# Kivipallur_joonis1.net
KiCad netlist of a schematic drawn in Altium Designer
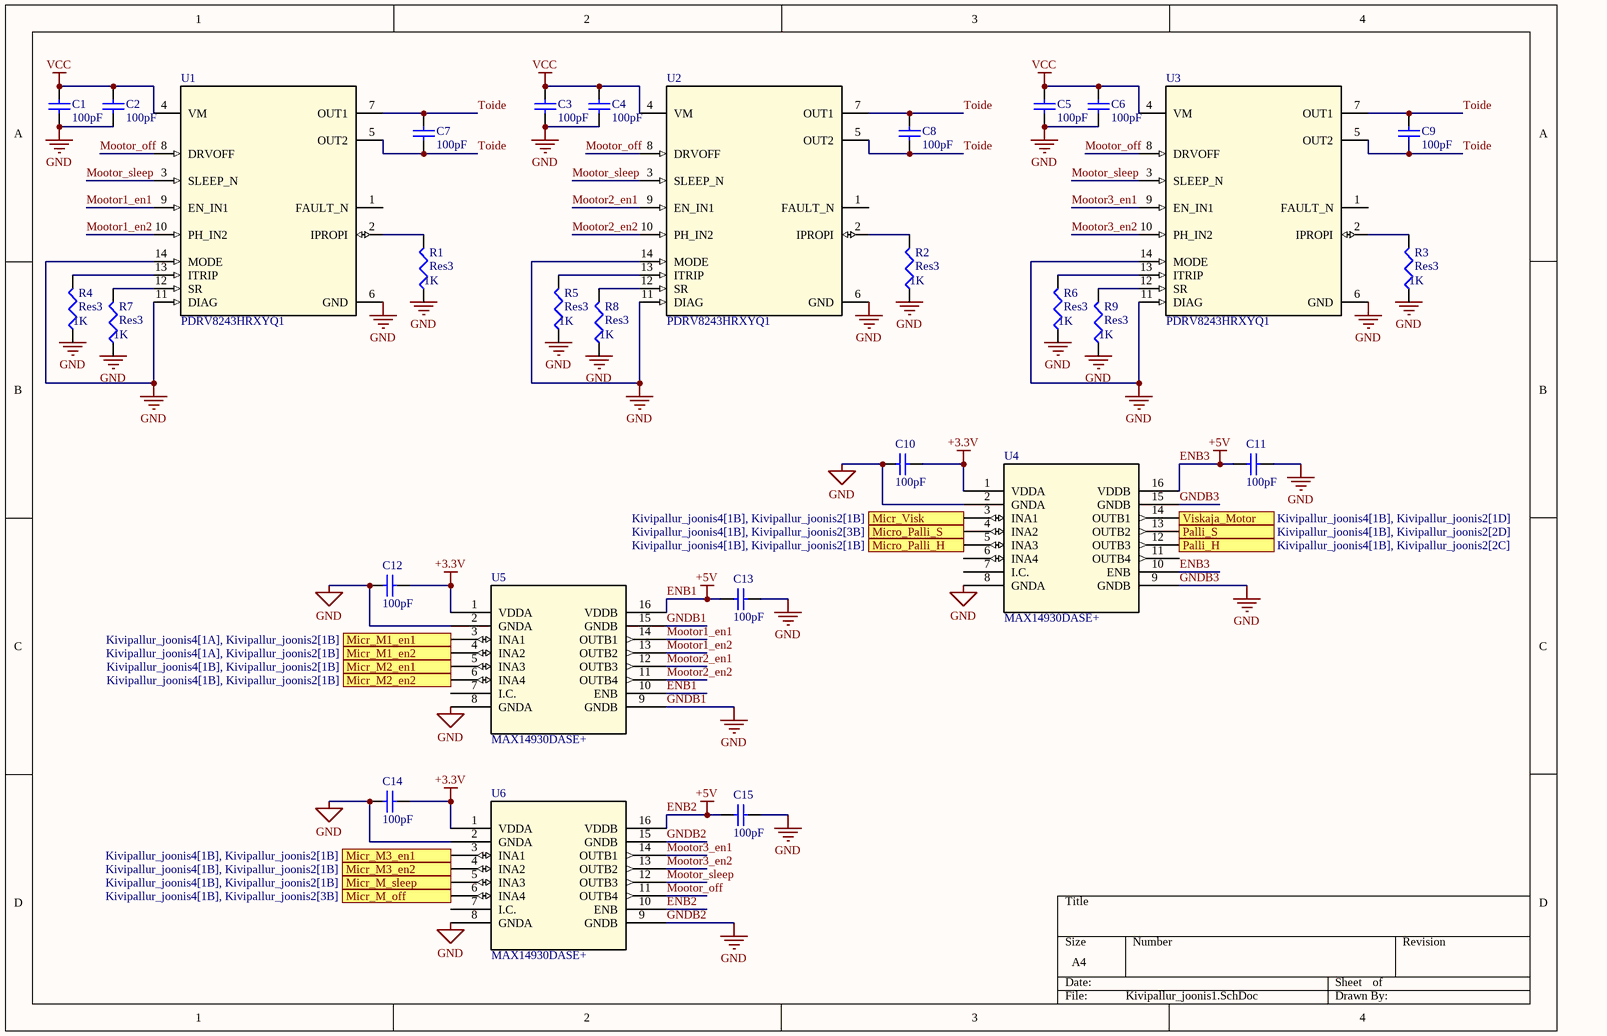
[diagram p0: Kivipallur_joonis1.SchDoc]

(export (version "E")
  (design (tool "Eeschema 10.0.6"))
  (components
    (comp (ref "C1")
      (value "100pF")
      (footprint "C1206")
      (description "Capacitor (Semiconductor SIM Model)")
      (fields (field (name "Comment") "Cap Semi") (field (name "PUBLISHER") "Altium Limited"))
      (libsource (lib "Miscellaneous Devices") (part "Cap Semi"))
    )
    (comp (ref "C2")
      (value "100pF")
      (footprint "C1206")
      (description "Capacitor (Semiconductor SIM Model)")
      (fields (field (name "Comment") "Cap Semi") (field (name "PUBLISHER") "Altium Limited"))
      (libsource (lib "Miscellaneous Devices") (part "Cap Semi"))
    )
    (comp (ref "C3")
      (value "100pF")
      (footprint "C1206")
      (description "Capacitor (Semiconductor SIM Model)")
      (fields (field (name "Comment") "Cap Semi") (field (name "PUBLISHER") "Altium Limited"))
      (libsource (lib "Miscellaneous Devices") (part "Cap Semi"))
    )
    (comp (ref "C4")
      (value "100pF")
      (footprint "C1206")
      (description "Capacitor (Semiconductor SIM Model)")
      (fields (field (name "Comment") "Cap Semi") (field (name "PUBLISHER") "Altium Limited"))
      (libsource (lib "Miscellaneous Devices") (part "Cap Semi"))
    )
    (comp (ref "C5")
      (value "100pF")
      (footprint "C1206")
      (description "Capacitor (Semiconductor SIM Model)")
      (fields (field (name "Comment") "Cap Semi") (field (name "PUBLISHER") "Altium Limited"))
      (libsource (lib "Miscellaneous Devices") (part "Cap Semi"))
    )
    (comp (ref "C6")
      (value "100pF")
      (footprint "C1206")
      (description "Capacitor (Semiconductor SIM Model)")
      (fields (field (name "Comment") "Cap Semi") (field (name "PUBLISHER") "Altium Limited"))
      (libsource (lib "Miscellaneous Devices") (part "Cap Semi"))
    )
    (comp (ref "C7")
      (value "100pF")
      (footprint "C1206")
      (description "Capacitor (Semiconductor SIM Model)")
      (fields (field (name "Comment") "Cap Semi") (field (name "PUBLISHER") "Altium Limited"))
      (libsource (lib "Miscellaneous Devices") (part "Cap Semi"))
    )
    (comp (ref "C8")
      (value "100pF")
      (footprint "C1206")
      (description "Capacitor (Semiconductor SIM Model)")
      (fields (field (name "Comment") "Cap Semi") (field (name "PUBLISHER") "Altium Limited"))
      (libsource (lib "Miscellaneous Devices") (part "Cap Semi"))
    )
    (comp (ref "C9")
      (value "100pF")
      (footprint "C1206")
      (description "Capacitor (Semiconductor SIM Model)")
      (fields (field (name "Comment") "Cap Semi") (field (name "PUBLISHER") "Altium Limited"))
      (libsource (lib "Miscellaneous Devices") (part "Cap Semi"))
    )
    (comp (ref "C10")
      (value "100pF")
      (footprint "C1206")
      (description "Capacitor (Semiconductor SIM Model)")
      (fields (field (name "Comment") "Cap Semi") (field (name "PUBLISHER") "Altium Limited"))
      (libsource (lib "Miscellaneous Devices") (part "Cap Semi"))
    )
    (comp (ref "C11")
      (value "100pF")
      (footprint "C1206")
      (description "Capacitor (Semiconductor SIM Model)")
      (fields (field (name "Comment") "Cap Semi") (field (name "PUBLISHER") "Altium Limited"))
      (libsource (lib "Miscellaneous Devices") (part "Cap Semi"))
    )
    (comp (ref "C12")
      (value "100pF")
      (footprint "C1206")
      (description "Capacitor (Semiconductor SIM Model)")
      (fields (field (name "Comment") "Cap Semi") (field (name "PUBLISHER") "Altium Limited"))
      (libsource (lib "Miscellaneous Devices") (part "Cap Semi"))
    )
    (comp (ref "C13")
      (value "100pF")
      (footprint "C1206")
      (description "Capacitor (Semiconductor SIM Model)")
      (fields (field (name "Comment") "Cap Semi") (field (name "PUBLISHER") "Altium Limited"))
      (libsource (lib "Miscellaneous Devices") (part "Cap Semi"))
    )
    (comp (ref "C14")
      (value "100pF")
      (footprint "C1206")
      (description "Capacitor (Semiconductor SIM Model)")
      (fields (field (name "Comment") "Cap Semi") (field (name "PUBLISHER") "Altium Limited"))
      (libsource (lib "Miscellaneous Devices") (part "Cap Semi"))
    )
    (comp (ref "C15")
      (value "100pF")
      (footprint "C1206")
      (description "Capacitor (Semiconductor SIM Model)")
      (fields (field (name "Comment") "Cap Semi") (field (name "PUBLISHER") "Altium Limited"))
      (libsource (lib "Miscellaneous Devices") (part "Cap Semi"))
    )
    (comp (ref "R1")
      (value "Res3")
      (footprint "J1-0603")
      (description "Resistor")
      (fields (field (name "ALTIUM_VALUE") "1K") (field (name "PUBLISHER") "Altium Limited"))
      (libsource (lib "Miscellaneous Devices") (part "Res3"))
    )
    (comp (ref "R2")
      (value "Res3")
      (footprint "J1-0603")
      (description "Resistor")
      (fields (field (name "ALTIUM_VALUE") "1K") (field (name "PUBLISHER") "Altium Limited"))
      (libsource (lib "Miscellaneous Devices") (part "Res3"))
    )
    (comp (ref "R3")
      (value "Res3")
      (footprint "J1-0603")
      (description "Resistor")
      (fields (field (name "ALTIUM_VALUE") "1K") (field (name "PUBLISHER") "Altium Limited"))
      (libsource (lib "Miscellaneous Devices") (part "Res3"))
    )
    (comp (ref "R4")
      (value "Res3")
      (footprint "J1-0603")
      (description "Resistor")
      (fields (field (name "ALTIUM_VALUE") "1K") (field (name "PUBLISHER") "Altium Limited"))
      (libsource (lib "Miscellaneous Devices") (part "Res3"))
    )
    (comp (ref "R5")
      (value "Res3")
      (footprint "J1-0603")
      (description "Resistor")
      (fields (field (name "ALTIUM_VALUE") "1K") (field (name "PUBLISHER") "Altium Limited"))
      (libsource (lib "Miscellaneous Devices") (part "Res3"))
    )
    (comp (ref "R6")
      (value "Res3")
      (footprint "J1-0603")
      (description "Resistor")
      (fields (field (name "ALTIUM_VALUE") "1K") (field (name "PUBLISHER") "Altium Limited"))
      (libsource (lib "Miscellaneous Devices") (part "Res3"))
    )
    (comp (ref "R7")
      (value "Res3")
      (footprint "J1-0603")
      (description "Resistor")
      (fields (field (name "ALTIUM_VALUE") "1K") (field (name "PUBLISHER") "Altium Limited"))
      (libsource (lib "Miscellaneous Devices") (part "Res3"))
    )
    (comp (ref "R8")
      (value "Res3")
      (footprint "J1-0603")
      (description "Resistor")
      (fields (field (name "ALTIUM_VALUE") "1K") (field (name "PUBLISHER") "Altium Limited"))
      (libsource (lib "Miscellaneous Devices") (part "Res3"))
    )
    (comp (ref "R9")
      (value "Res3")
      (footprint "J1-0603")
      (description "Resistor")
      (fields (field (name "ALTIUM_VALUE") "1K") (field (name "PUBLISHER") "Altium Limited"))
      (libsource (lib "Miscellaneous Devices") (part "Res3"))
    )
    (comp (ref "U1")
      (value "PDRV8243HRXYQ1")
      (footprint "RXY0014A-MFG")
      (description "No Description Available")
      (fields (field (name "COPYRIGHT") "Copyright (C) 2022 Ultra Librarian. All rights reserved."))
      (libsource (lib "PDRV8243HRXYQ1") (part "PDRV8243HRXYQ1"))
    )
    (comp (ref "U2")
      (value "PDRV8243HRXYQ1")
      (footprint "RXY0014A-MFG")
      (description "No Description Available")
      (fields (field (name "COPYRIGHT") "Copyright (C) 2022 Ultra Librarian. All rights reserved."))
      (libsource (lib "PDRV8243HRXYQ1") (part "PDRV8243HRXYQ1"))
    )
    (comp (ref "U3")
      (value "PDRV8243HRXYQ1")
      (footprint "RXY0014A-MFG")
      (description "No Description Available")
      (fields (field (name "COPYRIGHT") "Copyright (C) 2022 Ultra Librarian. All rights reserved."))
      (libsource (lib "PDRV8243HRXYQ1") (part "PDRV8243HRXYQ1"))
    )
    (comp (ref "U4")
      (value "MAX14930DASE+")
      (footprint "21-0041_S16+1_MXM")
      (description "No Description Available")
      (fields (field (name "COPYRIGHT") "Copyright (C) 2022 Ultra Librarian. All rights reserved."))
      (libsource (lib "MAX14930DASE&plus_") (part "MAX14930DASE+"))
    )
    (comp (ref "U5")
      (value "MAX14930DASE+")
      (footprint "21-0041_S16+1_MXM")
      (description "No Description Available")
      (fields (field (name "COPYRIGHT") "Copyright (C) 2022 Ultra Librarian. All rights reserved."))
      (libsource (lib "MAX14930DASE&plus_") (part "MAX14930DASE+"))
    )
    (comp (ref "U6")
      (value "MAX14930DASE+")
      (footprint "21-0041_S16+1_MXM")
      (description "No Description Available")
      (fields (field (name "COPYRIGHT") "Copyright (C) 2022 Ultra Librarian. All rights reserved."))
      (libsource (lib "MAX14930DASE&plus_") (part "MAX14930DASE+"))
    )
  )
  (nets
    (net (code "1") (name "+3.3V") (class "Default")
      (node (ref "C10") (pin "2") (pinfunction "2_2") (pintype "passive"))
      (node (ref "C12") (pin "2") (pinfunction "2_2") (pintype "passive"))
      (node (ref "C14") (pin "2") (pinfunction "2_2") (pintype "passive"))
      (node (ref "U4") (pin "1") (pinfunction "VDDA_1") (pintype "power_in"))
      (node (ref "U5") (pin "1") (pinfunction "VDDA_1") (pintype "power_in"))
      (node (ref "U6") (pin "1") (pinfunction "VDDA_1") (pintype "power_in"))
    )
    (net (code "2") (name "+5V") (class "Default")
      (node (ref "C11") (pin "1") (pinfunction "1_1") (pintype "passive"))
      (node (ref "C13") (pin "1") (pinfunction "1_1") (pintype "passive"))
      (node (ref "C15") (pin "1") (pinfunction "1_1") (pintype "passive"))
      (node (ref "U4") (pin "10") (pinfunction "ENB_10") (pintype "passive"))
      (node (ref "U4") (pin "16") (pinfunction "VDDB_16") (pintype "power_in"))
      (node (ref "U5") (pin "10") (pinfunction "ENB_10") (pintype "passive"))
      (node (ref "U5") (pin "16") (pinfunction "VDDB_16") (pintype "power_in"))
      (node (ref "U6") (pin "10") (pinfunction "ENB_10") (pintype "passive"))
      (node (ref "U6") (pin "16") (pinfunction "VDDB_16") (pintype "power_in"))
    )
    (net (code "3") (name "/Micr_M1_en1") (class "Default")
      (node (ref "U5") (pin "3") (pinfunction "INA1_3") (pintype "bidirectional"))
    )
    (net (code "4") (name "/Micr_M1_en2") (class "Default")
      (node (ref "U5") (pin "4") (pinfunction "INA2_4") (pintype "bidirectional"))
    )
    (net (code "5") (name "/Micr_M2_en1") (class "Default")
      (node (ref "U5") (pin "5") (pinfunction "INA3_5") (pintype "bidirectional"))
    )
    (net (code "6") (name "/Micr_M2_en2") (class "Default")
      (node (ref "U5") (pin "6") (pinfunction "INA4_6") (pintype "bidirectional"))
    )
    (net (code "7") (name "/Micr_M3_en1") (class "Default")
      (node (ref "U6") (pin "3") (pinfunction "INA1_3") (pintype "bidirectional"))
    )
    (net (code "8") (name "/Micr_M3_en2") (class "Default")
      (node (ref "U6") (pin "4") (pinfunction "INA2_4") (pintype "bidirectional"))
    )
    (net (code "9") (name "/Micr_M_off") (class "Default")
      (node (ref "U6") (pin "6") (pinfunction "INA4_6") (pintype "bidirectional"))
    )
    (net (code "10") (name "/Micr_M_sleep") (class "Default")
      (node (ref "U6") (pin "5") (pinfunction "INA3_5") (pintype "bidirectional"))
    )
    (net (code "11") (name "/Micr_Visk") (class "Default")
      (node (ref "U4") (pin "3") (pinfunction "INA1_3") (pintype "bidirectional"))
    )
    (net (code "12") (name "/Micro_Palli_H") (class "Default")
      (node (ref "U4") (pin "5") (pinfunction "INA3_5") (pintype "bidirectional"))
    )
    (net (code "13") (name "/Micro_Palli_S") (class "Default")
      (node (ref "U4") (pin "4") (pinfunction "INA2_4") (pintype "bidirectional"))
    )
    (net (code "14") (name "/Mootor1_en1") (class "Default")
      (node (ref "U1") (pin "9") (pinfunction "EN_IN1_9") (pintype "input"))
      (node (ref "U5") (pin "14") (pinfunction "OUTB1_14") (pintype "output"))
    )
    (net (code "15") (name "/Mootor1_en2") (class "Default")
      (node (ref "U1") (pin "10") (pinfunction "PH_IN2_10") (pintype "input"))
      (node (ref "U5") (pin "13") (pinfunction "OUTB2_13") (pintype "output"))
    )
    (net (code "16") (name "/Mootor2_en1") (class "Default")
      (node (ref "U2") (pin "9") (pinfunction "EN_IN1_9") (pintype "input"))
      (node (ref "U5") (pin "12") (pinfunction "OUTB3_12") (pintype "output"))
    )
    (net (code "17") (name "/Mootor2_en2") (class "Default")
      (node (ref "U2") (pin "10") (pinfunction "PH_IN2_10") (pintype "input"))
      (node (ref "U5") (pin "11") (pinfunction "OUTB4_11") (pintype "output"))
    )
    (net (code "18") (name "/Mootor3_en1") (class "Default")
      (node (ref "U3") (pin "9") (pinfunction "EN_IN1_9") (pintype "input"))
      (node (ref "U6") (pin "14") (pinfunction "OUTB1_14") (pintype "output"))
    )
    (net (code "19") (name "/Mootor3_en2") (class "Default")
      (node (ref "U3") (pin "10") (pinfunction "PH_IN2_10") (pintype "input"))
      (node (ref "U6") (pin "13") (pinfunction "OUTB2_13") (pintype "output"))
    )
    (net (code "20") (name "/Mootor_off") (class "Default")
      (node (ref "U1") (pin "8") (pinfunction "DRVOFF_8") (pintype "input"))
      (node (ref "U2") (pin "8") (pinfunction "DRVOFF_8") (pintype "input"))
      (node (ref "U3") (pin "8") (pinfunction "DRVOFF_8") (pintype "input"))
      (node (ref "U6") (pin "11") (pinfunction "OUTB4_11") (pintype "output"))
    )
    (net (code "21") (name "/Mootor_sleep") (class "Default")
      (node (ref "U1") (pin "3") (pinfunction "SLEEP_N_3") (pintype "input"))
      (node (ref "U2") (pin "3") (pinfunction "SLEEP_N_3") (pintype "input"))
      (node (ref "U3") (pin "3") (pinfunction "SLEEP_N_3") (pintype "input"))
      (node (ref "U6") (pin "12") (pinfunction "OUTB3_12") (pintype "output"))
    )
    (net (code "22") (name "/Palli_H") (class "Default")
      (node (ref "U4") (pin "12") (pinfunction "OUTB3_12") (pintype "output"))
    )
    (net (code "23") (name "/Palli_S") (class "Default")
      (node (ref "U4") (pin "13") (pinfunction "OUTB2_13") (pintype "output"))
    )
    (net (code "24") (name "/Toide") (class "Default")
      (node (ref "C7") (pin "1") (pinfunction "1_1") (pintype "passive"))
      (node (ref "C7") (pin "2") (pinfunction "2_2") (pintype "passive"))
      (node (ref "C8") (pin "1") (pinfunction "1_1") (pintype "passive"))
      (node (ref "C8") (pin "2") (pinfunction "2_2") (pintype "passive"))
      (node (ref "C9") (pin "1") (pinfunction "1_1") (pintype "passive"))
      (node (ref "C9") (pin "2") (pinfunction "2_2") (pintype "passive"))
      (node (ref "U1") (pin "5") (pinfunction "OUT2_5") (pintype "passive"))
      (node (ref "U1") (pin "7") (pinfunction "OUT1_7") (pintype "passive"))
      (node (ref "U2") (pin "5") (pinfunction "OUT2_5") (pintype "passive"))
      (node (ref "U2") (pin "7") (pinfunction "OUT1_7") (pintype "passive"))
      (node (ref "U3") (pin "5") (pinfunction "OUT2_5") (pintype "passive"))
      (node (ref "U3") (pin "7") (pinfunction "OUT1_7") (pintype "passive"))
    )
    (net (code "25") (name "/Viskaja_Motor") (class "Default")
      (node (ref "U4") (pin "14") (pinfunction "OUTB1_14") (pintype "output"))
    )
    (net (code "26") (name "GND") (class "Default")
      (node (ref "C1") (pin "1") (pinfunction "1_1") (pintype "passive"))
      (node (ref "C10") (pin "1") (pinfunction "1_1") (pintype "passive"))
      (node (ref "C11") (pin "2") (pinfunction "2_2") (pintype "passive"))
      (node (ref "C12") (pin "1") (pinfunction "1_1") (pintype "passive"))
      (node (ref "C13") (pin "2") (pinfunction "2_2") (pintype "passive"))
      (node (ref "C14") (pin "1") (pinfunction "1_1") (pintype "passive"))
      (node (ref "C15") (pin "2") (pinfunction "2_2") (pintype "passive"))
      (node (ref "C2") (pin "1") (pinfunction "1_1") (pintype "passive"))
      (node (ref "C3") (pin "1") (pinfunction "1_1") (pintype "passive"))
      (node (ref "C4") (pin "1") (pinfunction "1_1") (pintype "passive"))
      (node (ref "C5") (pin "1") (pinfunction "1_1") (pintype "passive"))
      (node (ref "C6") (pin "1") (pinfunction "1_1") (pintype "passive"))
      (node (ref "U1") (pin "11") (pinfunction "DIAG_11") (pintype "input"))
      (node (ref "U1") (pin "14") (pinfunction "MODE_14") (pintype "input"))
      (node (ref "U1") (pin "6") (pinfunction "GND_6") (pintype "power_in"))
      (node (ref "U2") (pin "11") (pinfunction "DIAG_11") (pintype "input"))
      (node (ref "U2") (pin "14") (pinfunction "MODE_14") (pintype "input"))
      (node (ref "U2") (pin "6") (pinfunction "GND_6") (pintype "power_in"))
      (node (ref "U3") (pin "11") (pinfunction "DIAG_11") (pintype "input"))
      (node (ref "U3") (pin "14") (pinfunction "MODE_14") (pintype "input"))
      (node (ref "U3") (pin "6") (pinfunction "GND_6") (pintype "power_in"))
      (node (ref "U4") (pin "15") (pinfunction "GNDB_15") (pintype "passive"))
      (node (ref "U4") (pin "2") (pinfunction "GNDA_2") (pintype "passive"))
      (node (ref "U4") (pin "8") (pinfunction "GNDA_8") (pintype "passive"))
      (node (ref "U4") (pin "9") (pinfunction "GNDB_9") (pintype "passive"))
      (node (ref "U5") (pin "15") (pinfunction "GNDB_15") (pintype "passive"))
      (node (ref "U5") (pin "2") (pinfunction "GNDA_2") (pintype "passive"))
      (node (ref "U5") (pin "8") (pinfunction "GNDA_8") (pintype "passive"))
      (node (ref "U5") (pin "9") (pinfunction "GNDB_9") (pintype "passive"))
      (node (ref "U6") (pin "15") (pinfunction "GNDB_15") (pintype "passive"))
      (node (ref "U6") (pin "2") (pinfunction "GNDA_2") (pintype "passive"))
      (node (ref "U6") (pin "8") (pinfunction "GNDA_8") (pintype "passive"))
      (node (ref "U6") (pin "9") (pinfunction "GNDB_9") (pintype "passive"))
    )
    (net (code "27") (name "Net-(U1-IPROPI)") (class "Default")
      (node (ref "R1") (pin "2") (pinfunction "2_2") (pintype "passive"))
      (node (ref "U1") (pin "2") (pinfunction "IPROPI_2") (pintype "bidirectional"))
    )
    (net (code "28") (name "Net-(U1-ITRIP)") (class "Default")
      (node (ref "R4") (pin "2") (pinfunction "2_2") (pintype "passive"))
      (node (ref "U1") (pin "13") (pinfunction "ITRIP_13") (pintype "input"))
    )
    (net (code "29") (name "Net-(U1-SR)") (class "Default")
      (node (ref "R7") (pin "2") (pinfunction "2_2") (pintype "passive"))
      (node (ref "U1") (pin "12") (pinfunction "SR_12") (pintype "input"))
    )
    (net (code "30") (name "Net-(U2-IPROPI)") (class "Default")
      (node (ref "R2") (pin "2") (pinfunction "2_2") (pintype "passive"))
      (node (ref "U2") (pin "2") (pinfunction "IPROPI_2") (pintype "bidirectional"))
    )
    (net (code "31") (name "Net-(U2-ITRIP)") (class "Default")
      (node (ref "R5") (pin "2") (pinfunction "2_2") (pintype "passive"))
      (node (ref "U2") (pin "13") (pinfunction "ITRIP_13") (pintype "input"))
    )
    (net (code "32") (name "Net-(U2-SR)") (class "Default")
      (node (ref "R8") (pin "2") (pinfunction "2_2") (pintype "passive"))
      (node (ref "U2") (pin "12") (pinfunction "SR_12") (pintype "input"))
    )
    (net (code "33") (name "Net-(U3-IPROPI)") (class "Default")
      (node (ref "R3") (pin "2") (pinfunction "2_2") (pintype "passive"))
      (node (ref "U3") (pin "2") (pinfunction "IPROPI_2") (pintype "bidirectional"))
    )
    (net (code "34") (name "Net-(U3-ITRIP)") (class "Default")
      (node (ref "R6") (pin "2") (pinfunction "2_2") (pintype "passive"))
      (node (ref "U3") (pin "13") (pinfunction "ITRIP_13") (pintype "input"))
    )
    (net (code "35") (name "Net-(U3-SR)") (class "Default")
      (node (ref "R9") (pin "2") (pinfunction "2_2") (pintype "passive"))
      (node (ref "U3") (pin "12") (pinfunction "SR_12") (pintype "input"))
    )
    (net (code "36") (name "VCC") (class "Default")
      (node (ref "C1") (pin "2") (pinfunction "2_2") (pintype "passive"))
      (node (ref "C2") (pin "2") (pinfunction "2_2") (pintype "passive"))
      (node (ref "C3") (pin "2") (pinfunction "2_2") (pintype "passive"))
      (node (ref "C4") (pin "2") (pinfunction "2_2") (pintype "passive"))
      (node (ref "C5") (pin "2") (pinfunction "2_2") (pintype "passive"))
      (node (ref "C6") (pin "2") (pinfunction "2_2") (pintype "passive"))
      (node (ref "U1") (pin "4") (pinfunction "VM_4") (pintype "power_in"))
      (node (ref "U2") (pin "4") (pinfunction "VM_4") (pintype "power_in"))
      (node (ref "U3") (pin "4") (pinfunction "VM_4") (pintype "power_in"))
    )
    (net (code "37") (name "unconnected-(R1-Pad1)") (class "Default")
      (node (ref "R1") (pin "1") (pinfunction "1_1") (pintype "passive"))
    )
    (net (code "38") (name "unconnected-(R2-Pad1)") (class "Default")
      (node (ref "R2") (pin "1") (pinfunction "1_1") (pintype "passive"))
    )
    (net (code "39") (name "unconnected-(R3-Pad1)") (class "Default")
      (node (ref "R3") (pin "1") (pinfunction "1_1") (pintype "passive"))
    )
    (net (code "40") (name "unconnected-(R4-Pad1)") (class "Default")
      (node (ref "R4") (pin "1") (pinfunction "1_1") (pintype "passive"))
    )
    (net (code "41") (name "unconnected-(R5-Pad1)") (class "Default")
      (node (ref "R5") (pin "1") (pinfunction "1_1") (pintype "passive"))
    )
    (net (code "42") (name "unconnected-(R6-Pad1)") (class "Default")
      (node (ref "R6") (pin "1") (pinfunction "1_1") (pintype "passive"))
    )
    (net (code "43") (name "unconnected-(R7-Pad1)") (class "Default")
      (node (ref "R7") (pin "1") (pinfunction "1_1") (pintype "passive"))
    )
    (net (code "44") (name "unconnected-(R8-Pad1)") (class "Default")
      (node (ref "R8") (pin "1") (pinfunction "1_1") (pintype "passive"))
    )
    (net (code "45") (name "unconnected-(R9-Pad1)") (class "Default")
      (node (ref "R9") (pin "1") (pinfunction "1_1") (pintype "passive"))
    )
    (net (code "46") (name "unconnected-(U1-FAULT_N-Pad1)") (class "Default")
      (node (ref "U1") (pin "1") (pinfunction "FAULT_N_1") (pintype "open_collector"))
    )
    (net (code "47") (name "unconnected-(U2-FAULT_N-Pad1)") (class "Default")
      (node (ref "U2") (pin "1") (pinfunction "FAULT_N_1") (pintype "open_collector"))
    )
    (net (code "48") (name "unconnected-(U3-FAULT_N-Pad1)") (class "Default")
      (node (ref "U3") (pin "1") (pinfunction "FAULT_N_1") (pintype "open_collector"))
    )
    (net (code "49") (name "unconnected-(U4-I.C.-Pad7)") (class "Default")
      (node (ref "U4") (pin "7") (pinfunction "I.C._7") (pintype "passive"))
    )
    (net (code "50") (name "unconnected-(U4-INA4-Pad6)") (class "Default")
      (node (ref "U4") (pin "6") (pinfunction "INA4_6") (pintype "bidirectional"))
    )
    (net (code "51") (name "unconnected-(U4-OUTB4-Pad11)") (class "Default")
      (node (ref "U4") (pin "11") (pinfunction "OUTB4_11") (pintype "output"))
    )
    (net (code "52") (name "unconnected-(U5-I.C.-Pad7)") (class "Default")
      (node (ref "U5") (pin "7") (pinfunction "I.C._7") (pintype "passive"))
    )
    (net (code "53") (name "unconnected-(U6-I.C.-Pad7)") (class "Default")
      (node (ref "U6") (pin "7") (pinfunction "I.C._7") (pintype "passive"))
    )
  )
)
